# volume-control-rev-a.net
KiCad netlist of a schematic drawn in EAGLE
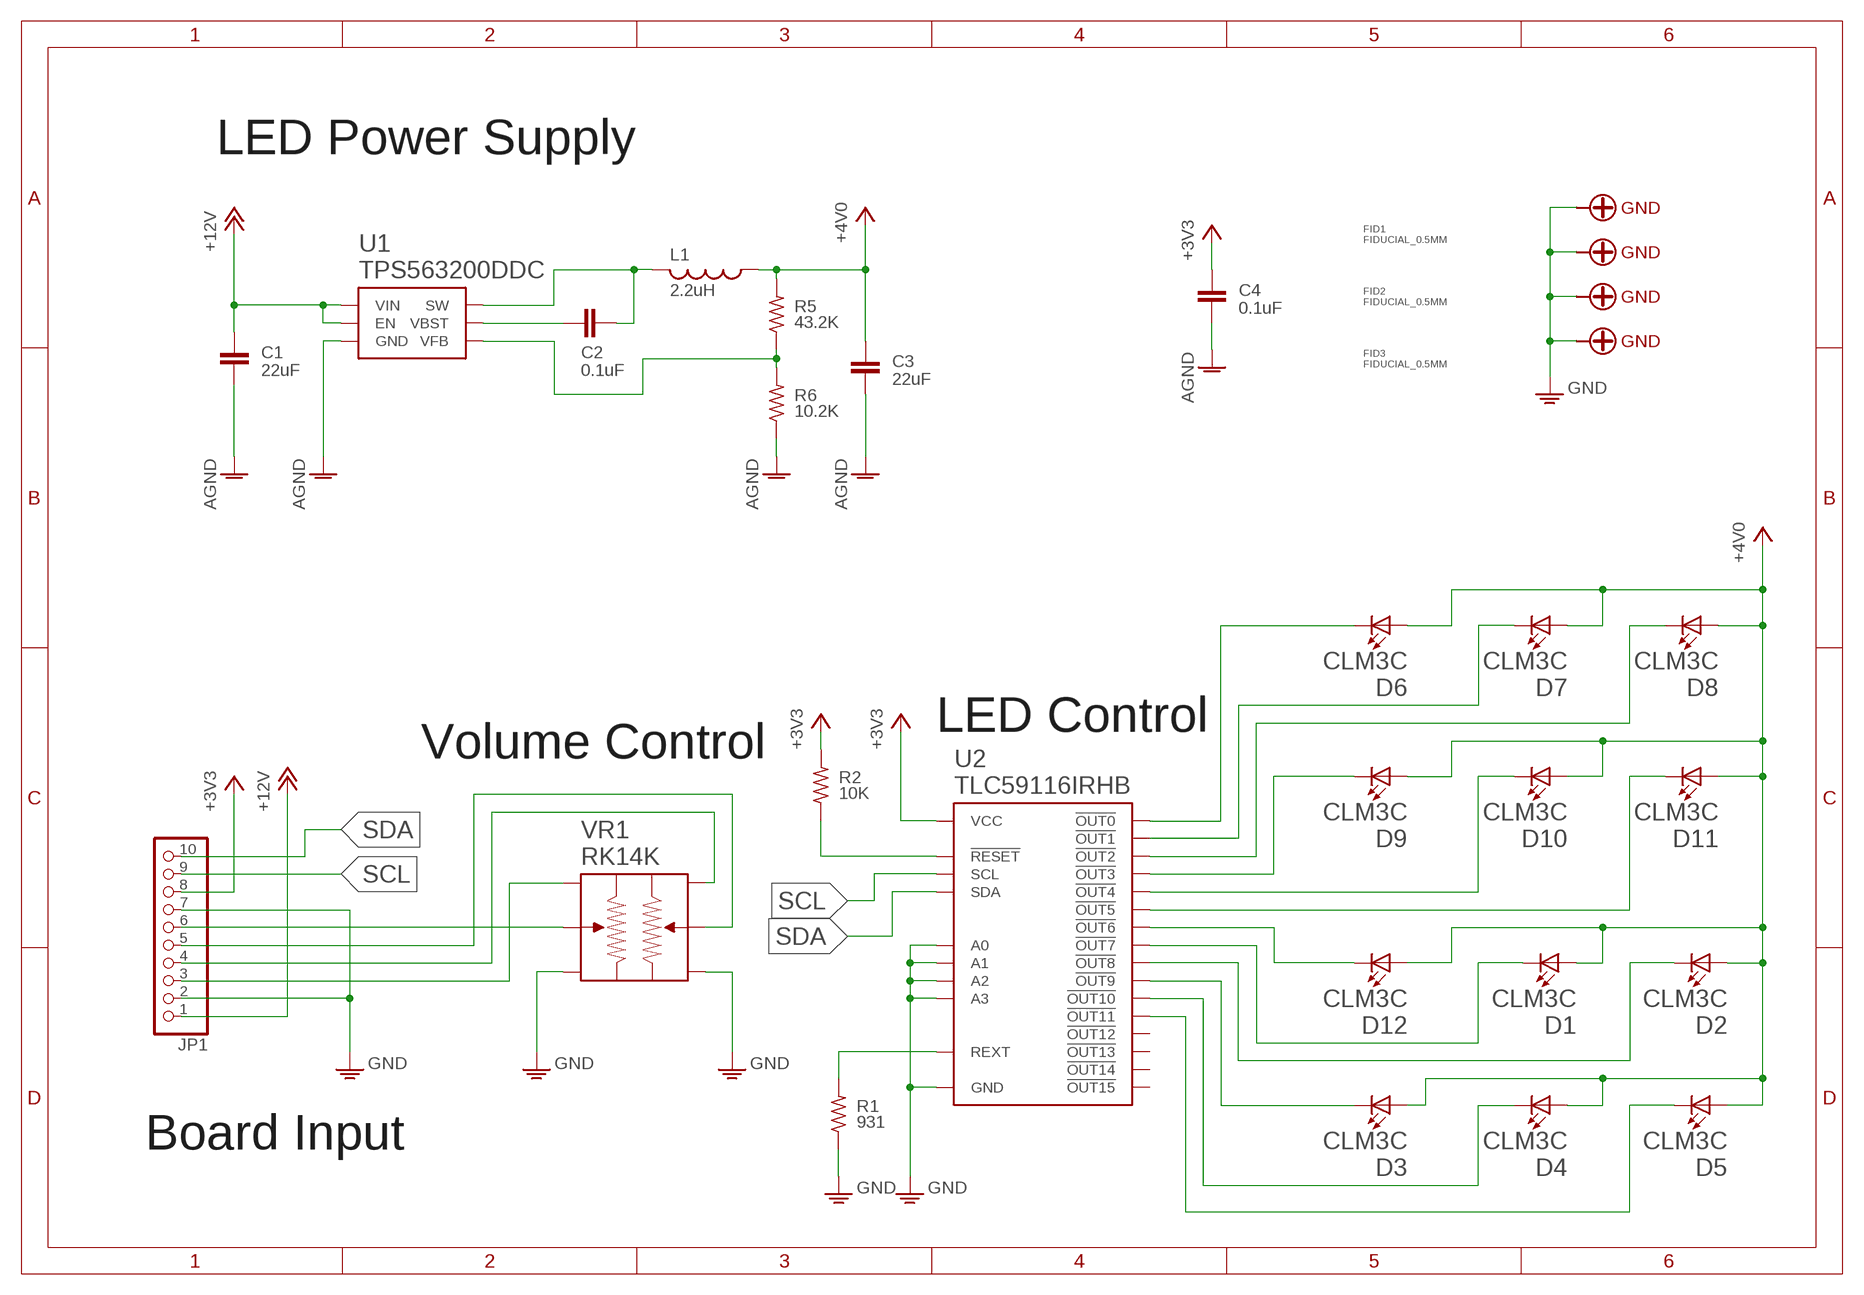
[diagram p0: schematic, sheet 1]

(export (version "E")
  (design (tool "Eeschema 10.0.6"))
  (components
    (comp (ref "AGND")
      (value "SCREW-THRU-GND-#4")
      (footprint "eagle-import:SCREW-THRU-GND-#4")
      (libsource (lib "eagle-import") (part "SCREW-THRU-GND-#4"))
    )
    (comp (ref "C1")
      (value "22uF")
      (footprint "eagle-import:C1210")
      (libsource (lib "eagle-import") (part "CAPACITOR-1210"))
    )
    (comp (ref "C2")
      (value "0.1uF")
      (footprint "eagle-import:C0603")
      (libsource (lib "eagle-import") (part "CAPACITOR-HORIZONTAL-0603"))
    )
    (comp (ref "C3")
      (value "22uF")
      (footprint "eagle-import:C1210")
      (libsource (lib "eagle-import") (part "CAPACITOR-1210"))
    )
    (comp (ref "C4")
      (value "0.1uF")
      (footprint "eagle-import:C0402")
      (libsource (lib "eagle-import") (part "CAPACITOR-0402"))
    )
    (comp (ref "D1")
      (value "CLM3C")
      (footprint "eagle-import:PLCC-2")
      (fields (field (name "MPN") "CLM3C-WKW-CXAYA453"))
      (libsource (lib "eagle-import") (part "CLM3C"))
    )
    (comp (ref "D2")
      (value "CLM3C")
      (footprint "eagle-import:PLCC-2")
      (fields (field (name "MPN") "CLM3C-WKW-CXAYA453"))
      (libsource (lib "eagle-import") (part "CLM3C"))
    )
    (comp (ref "D3")
      (value "CLM3C")
      (footprint "eagle-import:PLCC-2")
      (fields (field (name "MPN") "CLM3C-WKW-CXAYA453"))
      (libsource (lib "eagle-import") (part "CLM3C"))
    )
    (comp (ref "D4")
      (value "CLM3C")
      (footprint "eagle-import:PLCC-2")
      (fields (field (name "MPN") "CLM3C-WKW-CXAYA453"))
      (libsource (lib "eagle-import") (part "CLM3C"))
    )
    (comp (ref "D5")
      (value "CLM3C")
      (footprint "eagle-import:PLCC-2")
      (fields (field (name "MPN") "CLM3C-WKW-CXAYA453"))
      (libsource (lib "eagle-import") (part "CLM3C"))
    )
    (comp (ref "D6")
      (value "CLM3C")
      (footprint "eagle-import:PLCC-2")
      (fields (field (name "MPN") "CLM3C-WKW-CXAYA453"))
      (libsource (lib "eagle-import") (part "CLM3C"))
    )
    (comp (ref "D7")
      (value "CLM3C")
      (footprint "eagle-import:PLCC-2")
      (fields (field (name "MPN") "CLM3C-WKW-CXAYA453"))
      (libsource (lib "eagle-import") (part "CLM3C"))
    )
    (comp (ref "D8")
      (value "CLM3C")
      (footprint "eagle-import:PLCC-2")
      (fields (field (name "MPN") "CLM3C-WKW-CXAYA453"))
      (libsource (lib "eagle-import") (part "CLM3C"))
    )
    (comp (ref "D9")
      (value "CLM3C")
      (footprint "eagle-import:PLCC-2")
      (fields (field (name "MPN") "CLM3C-WKW-CXAYA453"))
      (libsource (lib "eagle-import") (part "CLM3C"))
    )
    (comp (ref "D10")
      (value "CLM3C")
      (footprint "eagle-import:PLCC-2")
      (fields (field (name "MPN") "CLM3C-WKW-CXAYA453"))
      (libsource (lib "eagle-import") (part "CLM3C"))
    )
    (comp (ref "D11")
      (value "CLM3C")
      (footprint "eagle-import:PLCC-2")
      (fields (field (name "MPN") "CLM3C-WKW-CXAYA453"))
      (libsource (lib "eagle-import") (part "CLM3C"))
    )
    (comp (ref "D12")
      (value "CLM3C")
      (footprint "eagle-import:PLCC-2")
      (fields (field (name "MPN") "CLM3C-WKW-CXAYA453"))
      (libsource (lib "eagle-import") (part "CLM3C"))
    )
    (comp (ref "FID1")
      (value "FIDUCIAL_0.5MM")
      (footprint "eagle-import:FIDUCIAL_0.5MM")
      (fields (field (name "HOUSEPART") "NO"))
      (libsource (lib "eagle-import") (part "FIDUCIAL_0.5MM"))
    )
    (comp (ref "FID2")
      (value "FIDUCIAL_0.5MM")
      (footprint "eagle-import:FIDUCIAL_0.5MM")
      (fields (field (name "HOUSEPART") "NO"))
      (libsource (lib "eagle-import") (part "FIDUCIAL_0.5MM"))
    )
    (comp (ref "FID3")
      (value "FIDUCIAL_0.5MM")
      (footprint "eagle-import:FIDUCIAL_0.5MM")
      (fields (field (name "HOUSEPART") "NO"))
      (libsource (lib "eagle-import") (part "FIDUCIAL_0.5MM"))
    )
    (comp (ref "JP1")
      (value "PINHD-1X10")
      (footprint "eagle-import:1X10")
      (fields (field (name "MPN") "22-05-3101"))
      (libsource (lib "eagle-import") (part "PINHD-1X10"))
    )
    (comp (ref "L1")
      (value "2.2uH")
      (footprint "eagle-import:COILCRAFT-XFL4020")
      (fields (field (name "MPN") "XFL4020-222MEB"))
      (libsource (lib "eagle-import") (part "INDUCTOR-HORIZONTALXFL4020"))
    )
    (comp (ref "R1")
      (value "931")
      (footprint "eagle-import:R0402")
      (libsource (lib "eagle-import") (part "RESISTOR-0402"))
    )
    (comp (ref "R2")
      (value "10K")
      (footprint "eagle-import:R0402")
      (libsource (lib "eagle-import") (part "RESISTOR-0402"))
    )
    (comp (ref "R5")
      (value "43.2K")
      (footprint "eagle-import:R0402")
      (libsource (lib "eagle-import") (part "RESISTOR-0402"))
    )
    (comp (ref "R6")
      (value "10.2K")
      (footprint "eagle-import:R0402")
      (libsource (lib "eagle-import") (part "RESISTOR-0402"))
    )
    (comp (ref "U$2")
      (value "SCREW-THRU-GND-#4")
      (footprint "eagle-import:SCREW-THRU-GND-#4")
      (libsource (lib "eagle-import") (part "SCREW-THRU-GND-#4"))
    )
    (comp (ref "U$3")
      (value "SCREW-THRU-GND-#4")
      (footprint "eagle-import:SCREW-THRU-GND-#4")
      (libsource (lib "eagle-import") (part "SCREW-THRU-GND-#4"))
    )
    (comp (ref "U$4")
      (value "SCREW-THRU-GND-#4")
      (footprint "eagle-import:SCREW-THRU-GND-#4")
      (libsource (lib "eagle-import") (part "SCREW-THRU-GND-#4"))
    )
    (comp (ref "U1")
      (value "TPS563200DDC")
      (footprint "eagle-import:R-PDSO-G6-DBV")
      (fields (field (name "MPN") "TPS563200DDCT"))
      (libsource (lib "eagle-import") (part "TPS562200DDC"))
    )
    (comp (ref "U2")
      (value "TLC59116IRHB")
      (footprint "eagle-import:S-PVQFN-N32-RHB")
      (libsource (lib "eagle-import") (part "TLC59116IRHB"))
    )
    (comp (ref "VR1")
      (value "RK14K")
      (footprint "eagle-import:RK14K")
      (libsource (lib "eagle-import") (part "RK14K"))
    )
  )
  (nets
    (net (code "1") (name "+3V3") (class "Default")
      (node (ref "C4") (pin "1") (pinfunction "1_1") (pintype "passive"))
      (node (ref "JP1") (pin "8") (pinfunction "8_8") (pintype "passive"))
      (node (ref "R2") (pin "2") (pinfunction "2_2") (pintype "passive"))
      (node (ref "U2") (pin "P$27") (pinfunction "VCC_P$27") (pintype "power_in"))
    )
    (net (code "2") (name "+4V0") (class "Default")
      (node (ref "C3") (pin "1") (pinfunction "1_1") (pintype "passive"))
      (node (ref "D1") (pin "ANODE") (pinfunction "A_ANODE") (pintype "passive"))
      (node (ref "D10") (pin "ANODE") (pinfunction "A_ANODE") (pintype "passive"))
      (node (ref "D11") (pin "ANODE") (pinfunction "A_ANODE") (pintype "passive"))
      (node (ref "D12") (pin "ANODE") (pinfunction "A_ANODE") (pintype "passive"))
      (node (ref "D2") (pin "ANODE") (pinfunction "A_ANODE") (pintype "passive"))
      (node (ref "D3") (pin "ANODE") (pinfunction "A_ANODE") (pintype "passive"))
      (node (ref "D4") (pin "ANODE") (pinfunction "A_ANODE") (pintype "passive"))
      (node (ref "D5") (pin "ANODE") (pinfunction "A_ANODE") (pintype "passive"))
      (node (ref "D6") (pin "ANODE") (pinfunction "A_ANODE") (pintype "passive"))
      (node (ref "D7") (pin "ANODE") (pinfunction "A_ANODE") (pintype "passive"))
      (node (ref "D8") (pin "ANODE") (pinfunction "A_ANODE") (pintype "passive"))
      (node (ref "D9") (pin "ANODE") (pinfunction "A_ANODE") (pintype "passive"))
      (node (ref "L1") (pin "P$1") (pinfunction "1_P$1") (pintype "passive"))
      (node (ref "R5") (pin "2") (pinfunction "2_2") (pintype "passive"))
    )
    (net (code "3") (name "+12V") (class "Default")
      (node (ref "C1") (pin "1") (pinfunction "1_1") (pintype "passive"))
      (node (ref "JP1") (pin "1") (pinfunction "1_1") (pintype "passive"))
      (node (ref "U1") (pin "3") (pinfunction "VIN_3") (pintype "bidirectional"))
      (node (ref "U1") (pin "5") (pinfunction "EN_5") (pintype "bidirectional"))
    )
    (net (code "4") (name "AGND") (class "Default")
      (node (ref "C1") (pin "2") (pinfunction "2_2") (pintype "passive"))
      (node (ref "C3") (pin "2") (pinfunction "2_2") (pintype "passive"))
      (node (ref "C4") (pin "2") (pinfunction "2_2") (pintype "passive"))
      (node (ref "R6") (pin "1") (pinfunction "1_1") (pintype "passive"))
      (node (ref "U1") (pin "1") (pinfunction "GND_1") (pintype "bidirectional"))
    )
    (net (code "5") (name "GND") (class "Default")
      (node (ref "AGND") (pin "P$1") (pinfunction "GND_P$1") (pintype "power_in"))
      (node (ref "AGND") (pin "P$2") (pinfunction "GND_P$2") (pintype "power_in"))
      (node (ref "AGND") (pin "P$3") (pinfunction "GND_P$3") (pintype "power_in"))
      (node (ref "AGND") (pin "P$4") (pinfunction "GND_P$4") (pintype "power_in"))
      (node (ref "AGND") (pin "P$5") (pinfunction "GND_P$5") (pintype "power_in"))
      (node (ref "AGND") (pin "P$6") (pinfunction "GND_P$6") (pintype "power_in"))
      (node (ref "AGND") (pin "P$7") (pinfunction "GND_P$7") (pintype "power_in"))
      (node (ref "AGND") (pin "P$8") (pinfunction "GND_P$8") (pintype "power_in"))
      (node (ref "AGND") (pin "P$9") (pinfunction "GND_P$9") (pintype "power_in"))
      (node (ref "JP1") (pin "2") (pinfunction "2_2") (pintype "passive"))
      (node (ref "JP1") (pin "7") (pinfunction "7_7") (pintype "passive"))
      (node (ref "R1") (pin "1") (pinfunction "1_1") (pintype "passive"))
      (node (ref "U$2") (pin "P$1") (pinfunction "GND_P$1") (pintype "power_in"))
      (node (ref "U$2") (pin "P$2") (pinfunction "GND_P$2") (pintype "power_in"))
      (node (ref "U$2") (pin "P$3") (pinfunction "GND_P$3") (pintype "power_in"))
      (node (ref "U$2") (pin "P$4") (pinfunction "GND_P$4") (pintype "power_in"))
      (node (ref "U$2") (pin "P$5") (pinfunction "GND_P$5") (pintype "power_in"))
      (node (ref "U$2") (pin "P$6") (pinfunction "GND_P$6") (pintype "power_in"))
      (node (ref "U$2") (pin "P$7") (pinfunction "GND_P$7") (pintype "power_in"))
      (node (ref "U$2") (pin "P$8") (pinfunction "GND_P$8") (pintype "power_in"))
      (node (ref "U$2") (pin "P$9") (pinfunction "GND_P$9") (pintype "power_in"))
      (node (ref "U$3") (pin "P$1") (pinfunction "GND_P$1") (pintype "power_in"))
      (node (ref "U$3") (pin "P$2") (pinfunction "GND_P$2") (pintype "power_in"))
      (node (ref "U$3") (pin "P$3") (pinfunction "GND_P$3") (pintype "power_in"))
      (node (ref "U$3") (pin "P$4") (pinfunction "GND_P$4") (pintype "power_in"))
      (node (ref "U$3") (pin "P$5") (pinfunction "GND_P$5") (pintype "power_in"))
      (node (ref "U$3") (pin "P$6") (pinfunction "GND_P$6") (pintype "power_in"))
      (node (ref "U$3") (pin "P$7") (pinfunction "GND_P$7") (pintype "power_in"))
      (node (ref "U$3") (pin "P$8") (pinfunction "GND_P$8") (pintype "power_in"))
      (node (ref "U$3") (pin "P$9") (pinfunction "GND_P$9") (pintype "power_in"))
      (node (ref "U$4") (pin "P$1") (pinfunction "GND_P$1") (pintype "power_in"))
      (node (ref "U$4") (pin "P$2") (pinfunction "GND_P$2") (pintype "power_in"))
      (node (ref "U$4") (pin "P$3") (pinfunction "GND_P$3") (pintype "power_in"))
      (node (ref "U$4") (pin "P$4") (pinfunction "GND_P$4") (pintype "power_in"))
      (node (ref "U$4") (pin "P$5") (pinfunction "GND_P$5") (pintype "power_in"))
      (node (ref "U$4") (pin "P$6") (pinfunction "GND_P$6") (pintype "power_in"))
      (node (ref "U$4") (pin "P$7") (pinfunction "GND_P$7") (pintype "power_in"))
      (node (ref "U$4") (pin "P$8") (pinfunction "GND_P$8") (pintype "power_in"))
      (node (ref "U$4") (pin "P$9") (pinfunction "GND_P$9") (pintype "power_in"))
      (node (ref "U2") (pin "P$1") (pinfunction "A2_P$1") (pintype "input"))
      (node (ref "U2") (pin "P$18") (pinfunction "GND_P$18") (pintype "power_in"))
      (node (ref "U2") (pin "P$2") (pinfunction "A3_P$2") (pintype "input"))
      (node (ref "U2") (pin "P$23") (pinfunction "GND_P$23") (pintype "power_in"))
      (node (ref "U2") (pin "P$31") (pinfunction "A0_P$31") (pintype "input"))
      (node (ref "U2") (pin "P$32") (pinfunction "A1_P$32") (pintype "input"))
      (node (ref "U2") (pin "P$7") (pinfunction "GND_P$7") (pintype "power_in"))
      (node (ref "U2") (pin "P$EP") (pinfunction "GND_P$EP") (pintype "power_in"))
      (node (ref "U2") (pin "P$EP1") (pinfunction "GND_P$EP1") (pintype "power_in"))
      (node (ref "U2") (pin "P$EP2") (pinfunction "GND_P$EP2") (pintype "power_in"))
      (node (ref "U2") (pin "P$EP3") (pinfunction "GND_P$EP3") (pintype "power_in"))
      (node (ref "U2") (pin "P$EP4") (pinfunction "GND_P$EP4") (pintype "power_in"))
      (node (ref "U2") (pin "P$EP5") (pinfunction "GND_P$EP5") (pintype "power_in"))
      (node (ref "VR1") (pin "L3") (pinfunction "OUT_L_L3") (pintype "bidirectional"))
      (node (ref "VR1") (pin "R3") (pinfunction "OUT_R_R3") (pintype "bidirectional"))
    )
    (net (code "6") (name "Net-(D1-C)") (class "Default")
      (node (ref "D1") (pin "CATHODE") (pinfunction "C_CATHODE") (pintype "passive"))
      (node (ref "U2") (pin "P$11") (pinfunction "~{OUT7}_P$11") (pintype "output"))
    )
    (net (code "7") (name "Net-(D2-C)") (class "Default")
      (node (ref "D2") (pin "CATHODE") (pinfunction "C_CATHODE") (pintype "passive"))
      (node (ref "U2") (pin "P$14") (pinfunction "~{OUT8}_P$14") (pintype "output"))
    )
    (net (code "8") (name "Net-(D3-C)") (class "Default")
      (node (ref "D3") (pin "CATHODE") (pinfunction "C_CATHODE") (pintype "passive"))
      (node (ref "U2") (pin "P$15") (pinfunction "~{OUT9}_P$15") (pintype "output"))
    )
    (net (code "9") (name "Net-(D4-C)") (class "Default")
      (node (ref "D4") (pin "CATHODE") (pinfunction "C_CATHODE") (pintype "passive"))
      (node (ref "U2") (pin "P$16") (pinfunction "~{OUT10}_P$16") (pintype "output"))
    )
    (net (code "10") (name "Net-(D5-C)") (class "Default")
      (node (ref "D5") (pin "CATHODE") (pinfunction "C_CATHODE") (pintype "passive"))
      (node (ref "U2") (pin "P$17") (pinfunction "~{OUT11}_P$17") (pintype "output"))
    )
    (net (code "11") (name "Net-(D6-C)") (class "Default")
      (node (ref "D6") (pin "CATHODE") (pinfunction "C_CATHODE") (pintype "passive"))
      (node (ref "U2") (pin "P$3") (pinfunction "~{OUT0}_P$3") (pintype "output"))
    )
    (net (code "12") (name "Net-(D7-C)") (class "Default")
      (node (ref "D7") (pin "CATHODE") (pinfunction "C_CATHODE") (pintype "passive"))
      (node (ref "U2") (pin "P$4") (pinfunction "~{OUT1}_P$4") (pintype "output"))
    )
    (net (code "13") (name "Net-(D8-C)") (class "Default")
      (node (ref "D8") (pin "CATHODE") (pinfunction "C_CATHODE") (pintype "passive"))
      (node (ref "U2") (pin "P$5") (pinfunction "~{OUT2}_P$5") (pintype "output"))
    )
    (net (code "14") (name "Net-(D9-C)") (class "Default")
      (node (ref "D9") (pin "CATHODE") (pinfunction "C_CATHODE") (pintype "passive"))
      (node (ref "U2") (pin "P$6") (pinfunction "~{OUT3}_P$6") (pintype "output"))
    )
    (net (code "15") (name "Net-(D10-C)") (class "Default")
      (node (ref "D10") (pin "CATHODE") (pinfunction "C_CATHODE") (pintype "passive"))
      (node (ref "U2") (pin "P$8") (pinfunction "~{OUT4}_P$8") (pintype "output"))
    )
    (net (code "16") (name "Net-(D11-C)") (class "Default")
      (node (ref "D11") (pin "CATHODE") (pinfunction "C_CATHODE") (pintype "passive"))
      (node (ref "U2") (pin "P$9") (pinfunction "~{OUT5}_P$9") (pintype "output"))
    )
    (net (code "17") (name "Net-(D12-C)") (class "Default")
      (node (ref "D12") (pin "CATHODE") (pinfunction "C_CATHODE") (pintype "passive"))
      (node (ref "U2") (pin "P$10") (pinfunction "~{OUT6}_P$10") (pintype "output"))
    )
    (net (code "18") (name "Net-(L1-2)") (class "Default")
      (node (ref "C2") (pin "2") (pinfunction "2_2") (pintype "passive"))
      (node (ref "L1") (pin "P$2") (pinfunction "2_P$2") (pintype "passive"))
      (node (ref "U1") (pin "2") (pinfunction "SW_2") (pintype "bidirectional"))
    )
    (net (code "19") (name "Net-(U1-VBST)") (class "Default")
      (node (ref "C2") (pin "1") (pinfunction "1_1") (pintype "passive"))
      (node (ref "U1") (pin "6") (pinfunction "VBST_6") (pintype "bidirectional"))
    )
    (net (code "20") (name "Net-(U1-VFB)") (class "Default")
      (node (ref "R5") (pin "1") (pinfunction "1_1") (pintype "passive"))
      (node (ref "R6") (pin "2") (pinfunction "2_2") (pintype "passive"))
      (node (ref "U1") (pin "4") (pinfunction "VFB_4") (pintype "bidirectional"))
    )
    (net (code "21") (name "Net-(U2-REXT)") (class "Default")
      (node (ref "R1") (pin "2") (pinfunction "2_2") (pintype "passive"))
      (node (ref "U2") (pin "P$30") (pinfunction "REXT_P$30") (pintype "input"))
    )
    (net (code "22") (name "Net-(U2-~{RESET})") (class "Default")
      (node (ref "R2") (pin "1") (pinfunction "1_1") (pintype "passive"))
      (node (ref "U2") (pin "P$24") (pinfunction "~{RESET}_P$24") (pintype "input"))
    )
    (net (code "23") (name "Net-(VR1-IN_L)") (class "Default")
      (node (ref "JP1") (pin "3") (pinfunction "3_3") (pintype "passive"))
      (node (ref "VR1") (pin "L1") (pinfunction "IN_L_L1") (pintype "bidirectional"))
    )
    (net (code "24") (name "Net-(VR1-IN_R)") (class "Default")
      (node (ref "JP1") (pin "4") (pinfunction "4_4") (pintype "passive"))
      (node (ref "VR1") (pin "R1") (pinfunction "IN_R_R1") (pintype "bidirectional"))
    )
    (net (code "25") (name "Net-(VR1-WIPER_L)") (class "Default")
      (node (ref "JP1") (pin "6") (pinfunction "6_6") (pintype "passive"))
      (node (ref "VR1") (pin "L2") (pinfunction "WIPER_L_L2") (pintype "bidirectional"))
    )
    (net (code "26") (name "Net-(VR1-WIPER_R)") (class "Default")
      (node (ref "JP1") (pin "5") (pinfunction "5_5") (pintype "passive"))
      (node (ref "VR1") (pin "R2") (pinfunction "WIPER_R_R2") (pintype "bidirectional"))
    )
    (net (code "27") (name "SCL") (class "Default")
      (node (ref "JP1") (pin "9") (pinfunction "9_9") (pintype "passive"))
      (node (ref "U2") (pin "P$25") (pinfunction "SCL_P$25") (pintype "input"))
    )
    (net (code "28") (name "SDA") (class "Default")
      (node (ref "JP1") (pin "10") (pinfunction "10_10") (pintype "passive"))
      (node (ref "U2") (pin "P$26") (pinfunction "SDA_P$26") (pintype "bidirectional"))
    )
    (net (code "29") (name "unconnected-(U2-~{OUT12}-PadP$19)") (class "Default")
      (node (ref "U2") (pin "P$19") (pinfunction "~{OUT12}_P$19") (pintype "output"))
    )
    (net (code "30") (name "unconnected-(U2-~{OUT13}-PadP$20)") (class "Default")
      (node (ref "U2") (pin "P$20") (pinfunction "~{OUT13}_P$20") (pintype "output"))
    )
    (net (code "31") (name "unconnected-(U2-~{OUT14}-PadP$21)") (class "Default")
      (node (ref "U2") (pin "P$21") (pinfunction "~{OUT14}_P$21") (pintype "output"))
    )
    (net (code "32") (name "unconnected-(U2-~{OUT15}-PadP$22)") (class "Default")
      (node (ref "U2") (pin "P$22") (pinfunction "~{OUT15}_P$22") (pintype "output"))
    )
  )
)
